# PCB.net
KiCad netlist of a schematic drawn in Altium Designer
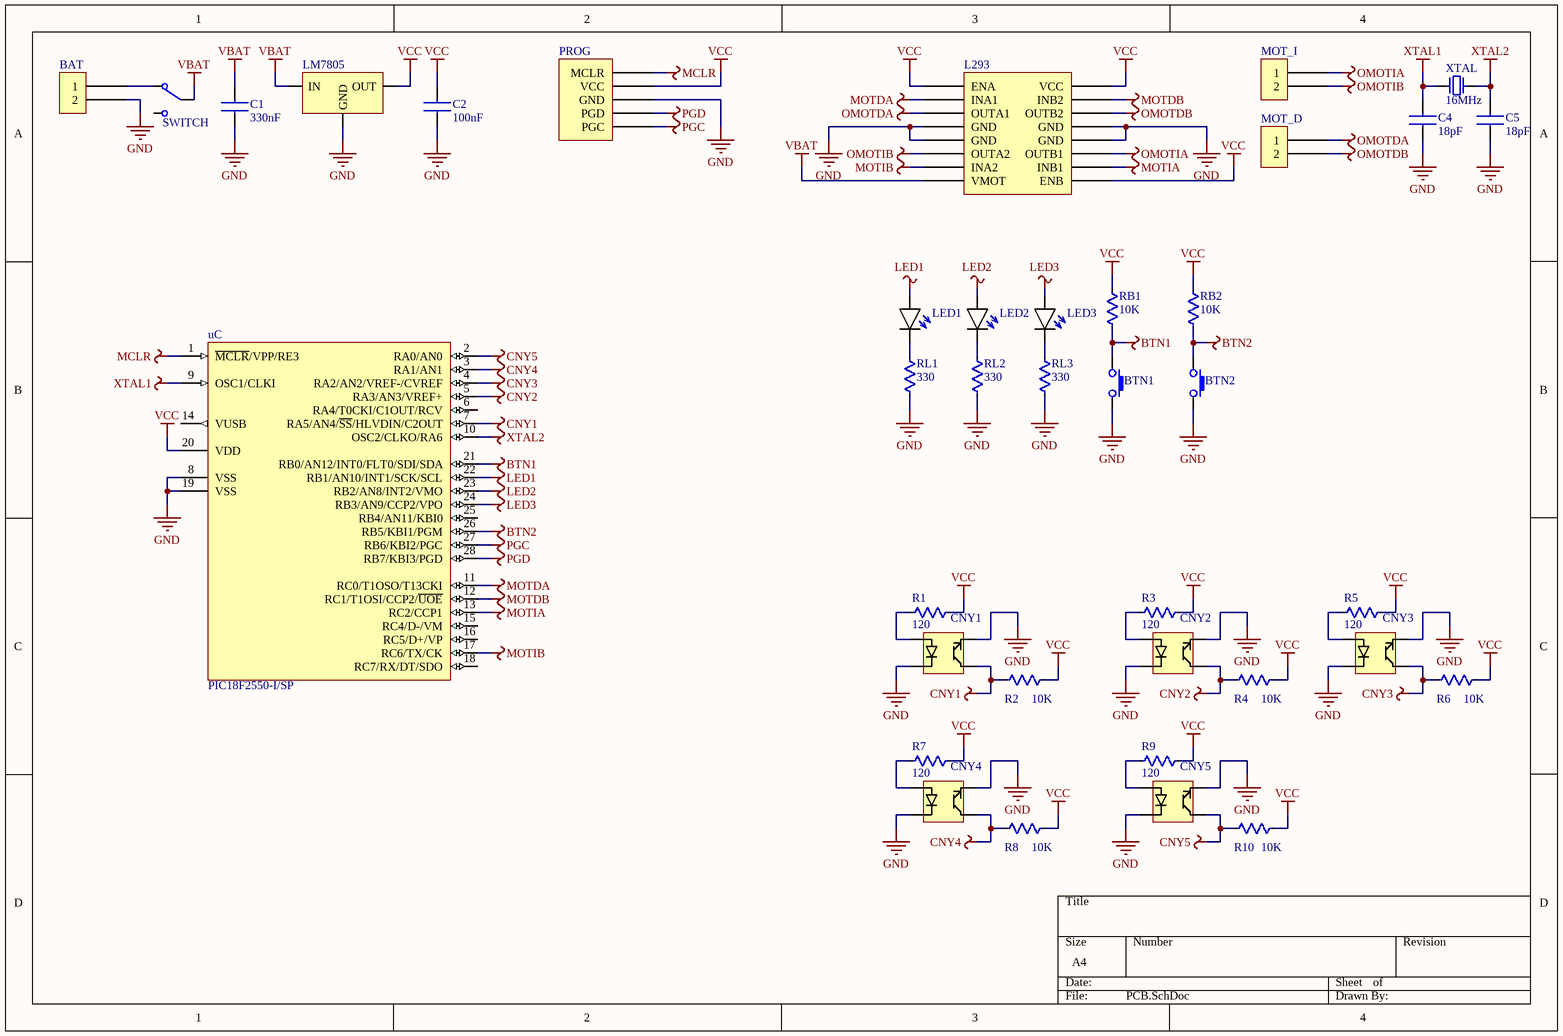
[diagram p0: PCB.SchDoc]

(export (version "E")
  (design (tool "Eeschema 10.0.6"))
  (components
    (comp (ref "BAT")
      (value "~")
      (footprint "HEADER 1x2")
      (libsource (lib "AltiumLibrary") (part "Header 1x2"))
    )
    (comp (ref "BTN1")
      (value "BUTTON_SMALL_4PIN")
      (footprint "TACT_SWITCH-SMALL-4PIN")
      (libsource (lib "AltiumLibrary") (part "BUTTON_SMALL_4PIN"))
    )
    (comp (ref "BTN2")
      (value "BUTTON_SMALL_4PIN")
      (footprint "TACT_SWITCH-SMALL-4PIN")
      (libsource (lib "AltiumLibrary") (part "BUTTON_SMALL_4PIN"))
    )
    (comp (ref "C1")
      (value "330nF")
      (footprint "CAP-CER")
      (fields (field (name "Comment") "CAP-CER"))
      (libsource (lib "AltiumLibrary") (part "CAP-CER"))
    )
    (comp (ref "C2")
      (value "100nF")
      (footprint "CAP-CER")
      (fields (field (name "Comment") "CAP-CER"))
      (libsource (lib "AltiumLibrary") (part "CAP-CER"))
    )
    (comp (ref "C4")
      (value "18pF")
      (footprint "CAP-CER")
      (fields (field (name "Comment") "CAP-CER"))
      (libsource (lib "AltiumLibrary") (part "CAP-CER"))
    )
    (comp (ref "C5")
      (value "18pF")
      (footprint "CAP-CER")
      (fields (field (name "Comment") "CAP-CER"))
      (libsource (lib "AltiumLibrary") (part "CAP-CER"))
    )
    (comp (ref "CNY1") (value "~") (footprint "CNY70") (libsource (lib "AltiumLibrary") (part "CNY70")))
    (comp (ref "CNY2") (value "~") (footprint "CNY70") (libsource (lib "AltiumLibrary") (part "CNY70")))
    (comp (ref "CNY3") (value "~") (footprint "CNY70") (libsource (lib "AltiumLibrary") (part "CNY70")))
    (comp (ref "CNY4") (value "~") (footprint "CNY70") (libsource (lib "AltiumLibrary") (part "CNY70")))
    (comp (ref "CNY5") (value "~") (footprint "CNY70") (libsource (lib "AltiumLibrary") (part "CNY70")))
    (comp (ref "L293") (value "L293") (footprint "DIP16") (libsource (lib "AltiumLibrary") (part "L293")))
    (comp (ref "LED1") (value "LED") (footprint "LED-3MM-RED") (libsource (lib "AltiumLibrary") (part "LED")))
    (comp (ref "LED2")
      (value "LED")
      (footprint "LED-3MM-YELLOW")
      (libsource (lib "AltiumLibrary") (part "LED"))
    )
    (comp (ref "LED3")
      (value "LED")
      (footprint "LED-3MM-GREEN")
      (libsource (lib "AltiumLibrary") (part "LED"))
    )
    (comp (ref "LM7805")
      (value "LM78XX")
      (footprint "TO-220-STRAIGHT")
      (libsource (lib "AltiumLibrary") (part "LM78XX"))
    )
    (comp (ref "MOT_D")
      (value "~")
      (footprint "HEADER 1x2")
      (libsource (lib "AltiumLibrary") (part "Header 1x2"))
    )
    (comp (ref "MOT_I")
      (value "~")
      (footprint "HEADER 1x2")
      (libsource (lib "AltiumLibrary") (part "Header 1x2"))
    )
    (comp (ref "PROG")
      (value "~")
      (footprint "Header 1x5")
      (libsource (lib "AltiumLibrary") (part "Header Programmer"))
    )
    (comp (ref "R1")
      (value "120")
      (footprint "RES-Axial-400mil")
      (fields (field (name "Comment") "RES"))
      (libsource (lib "AltiumLibrary") (part "RES"))
    )
    (comp (ref "R2")
      (value "10K")
      (footprint "RES-Axial-400mil")
      (fields (field (name "Comment") "RES"))
      (libsource (lib "AltiumLibrary") (part "RES"))
    )
    (comp (ref "R3")
      (value "120")
      (footprint "RES-Axial-400mil")
      (fields (field (name "Comment") "RES"))
      (libsource (lib "AltiumLibrary") (part "RES"))
    )
    (comp (ref "R4")
      (value "10K")
      (footprint "RES-Axial-400mil")
      (fields (field (name "Comment") "RES"))
      (libsource (lib "AltiumLibrary") (part "RES"))
    )
    (comp (ref "R5")
      (value "120")
      (footprint "RES-Axial-400mil")
      (fields (field (name "Comment") "RES"))
      (libsource (lib "AltiumLibrary") (part "RES"))
    )
    (comp (ref "R6")
      (value "10K")
      (footprint "RES-Axial-400mil")
      (fields (field (name "Comment") "RES"))
      (libsource (lib "AltiumLibrary") (part "RES"))
    )
    (comp (ref "R7")
      (value "120")
      (footprint "RES-Axial-400mil")
      (fields (field (name "Comment") "RES"))
      (libsource (lib "AltiumLibrary") (part "RES"))
    )
    (comp (ref "R8")
      (value "10K")
      (footprint "RES-Axial-400mil")
      (fields (field (name "Comment") "RES"))
      (libsource (lib "AltiumLibrary") (part "RES"))
    )
    (comp (ref "R9")
      (value "120")
      (footprint "RES-Axial-400mil")
      (fields (field (name "Comment") "RES"))
      (libsource (lib "AltiumLibrary") (part "RES"))
    )
    (comp (ref "R10")
      (value "10K")
      (footprint "RES-Axial-400mil")
      (fields (field (name "Comment") "RES"))
      (libsource (lib "AltiumLibrary") (part "RES"))
    )
    (comp (ref "RB1")
      (value "10K")
      (footprint "RES-Axial-400mil")
      (fields (field (name "Comment") "RES"))
      (libsource (lib "") (part "RES_1"))
    )
    (comp (ref "RB2")
      (value "10K")
      (footprint "RES-Axial-400mil")
      (fields (field (name "Comment") "RES"))
      (libsource (lib "") (part "RES_1"))
    )
    (comp (ref "RL1")
      (value "330")
      (footprint "RES-Axial-400mil")
      (fields (field (name "Comment") "RES"))
      (libsource (lib "") (part "RES_2"))
    )
    (comp (ref "RL2")
      (value "330")
      (footprint "RES-Axial-400mil")
      (fields (field (name "Comment") "RES"))
      (libsource (lib "") (part "RES_2"))
    )
    (comp (ref "RL3")
      (value "330")
      (footprint "RES-Axial-400mil")
      (fields (field (name "Comment") "RES"))
      (libsource (lib "") (part "RES_2"))
    )
    (comp (ref "SWITCH")
      (value "SLIDE-SWITCH")
      (footprint "SWITCH")
      (libsource (lib "AltiumLibrary") (part "SLIDE-SWITCH"))
    )
    (comp (ref "uC")
      (value "PIC18F2550-I/SP")
      (footprint "DIP28")
      (fields (field (name "PUBLISHER") "Altium Limited"))
      (libsource (lib "Microchip Microcontroller 8-Bit PIC18") (part "PIC18F2550-I/SP"))
    )
    (comp (ref "XTAL")
      (value "XTAL")
      (footprint "CRYSTAL-TH")
      (fields (field (name "FREQUENCY") "16MHz"))
      (libsource (lib "AltiumLibrary") (part "XTAL"))
    )
  )
  (nets
    (net (code "1") (name "BTN1") (class "Default")
      (node (ref "BTN1") (pin "1") (pintype "passive"))
      (node (ref "RB1") (pin "2") (pintype "passive"))
      (node (ref "uC") (pin "21") (pinfunction "RB0/AN12/INT0/FLT0/SDI/SDA_21") (pintype "bidirectional"))
    )
    (net (code "2") (name "BTN2") (class "Default")
      (node (ref "BTN2") (pin "1") (pintype "passive"))
      (node (ref "RB2") (pin "2") (pintype "passive"))
      (node (ref "uC") (pin "26") (pinfunction "RB5/KBI1/PGM_26") (pintype "bidirectional"))
    )
    (net (code "3") (name "CNY1") (class "Default")
      (node (ref "CNY1") (pin "C") (pinfunction "C_C") (pintype "passive"))
      (node (ref "R2") (pin "1") (pintype "passive"))
      (node (ref "uC") (pin "7") (pinfunction "RA5/AN4/~{SS}/HLVDIN/C2OUT_7") (pintype "bidirectional"))
    )
    (net (code "4") (name "CNY2") (class "Default")
      (node (ref "CNY2") (pin "C") (pinfunction "C_C") (pintype "passive"))
      (node (ref "R4") (pin "1") (pintype "passive"))
      (node (ref "uC") (pin "5") (pinfunction "RA3/AN3/VREF+_5") (pintype "bidirectional"))
    )
    (net (code "5") (name "CNY3") (class "Default")
      (node (ref "CNY3") (pin "C") (pinfunction "C_C") (pintype "passive"))
      (node (ref "R6") (pin "1") (pintype "passive"))
      (node (ref "uC") (pin "4") (pinfunction "RA2/AN2/VREF-/CVREF_4") (pintype "bidirectional"))
    )
    (net (code "6") (name "CNY4") (class "Default")
      (node (ref "CNY4") (pin "C") (pinfunction "C_C") (pintype "passive"))
      (node (ref "R8") (pin "1") (pintype "passive"))
      (node (ref "uC") (pin "3") (pinfunction "RA1/AN1_3") (pintype "bidirectional"))
    )
    (net (code "7") (name "CNY5") (class "Default")
      (node (ref "CNY5") (pin "C") (pinfunction "C_C") (pintype "passive"))
      (node (ref "R10") (pin "1") (pintype "passive"))
      (node (ref "uC") (pin "2") (pinfunction "RA0/AN0_2") (pintype "bidirectional"))
    )
    (net (code "8") (name "GND") (class "Default")
      (node (ref "BAT") (pin "2") (pinfunction "2_2") (pintype "passive"))
      (node (ref "BTN1") (pin "2") (pintype "passive"))
      (node (ref "BTN2") (pin "2") (pintype "passive"))
      (node (ref "C1") (pin "2") (pintype "passive"))
      (node (ref "C2") (pin "2") (pintype "passive"))
      (node (ref "C4") (pin "1") (pintype "passive"))
      (node (ref "C5") (pin "1") (pintype "passive"))
      (node (ref "CNY1") (pin "E") (pinfunction "7.5_E") (pintype "passive"))
      (node (ref "CNY1") (pin "K") (pinfunction "K_K") (pintype "passive"))
      (node (ref "CNY2") (pin "E") (pinfunction "7.5_E") (pintype "passive"))
      (node (ref "CNY2") (pin "K") (pinfunction "K_K") (pintype "passive"))
      (node (ref "CNY3") (pin "E") (pinfunction "7.5_E") (pintype "passive"))
      (node (ref "CNY3") (pin "K") (pinfunction "K_K") (pintype "passive"))
      (node (ref "CNY4") (pin "E") (pinfunction "7.5_E") (pintype "passive"))
      (node (ref "CNY4") (pin "K") (pinfunction "K_K") (pintype "passive"))
      (node (ref "CNY5") (pin "E") (pinfunction "7.5_E") (pintype "passive"))
      (node (ref "CNY5") (pin "K") (pinfunction "K_K") (pintype "passive"))
      (node (ref "L293") (pin "12") (pinfunction "GND_12") (pintype "passive"))
      (node (ref "L293") (pin "13") (pinfunction "GND_13") (pintype "passive"))
      (node (ref "L293") (pin "4") (pinfunction "GND_4") (pintype "passive"))
      (node (ref "L293") (pin "5") (pinfunction "GND_5") (pintype "passive"))
      (node (ref "LM7805") (pin "2") (pinfunction "GND_2") (pintype "power_in"))
      (node (ref "PROG") (pin "3") (pinfunction "GND_3") (pintype "power_in"))
      (node (ref "RL1") (pin "1") (pintype "passive"))
      (node (ref "RL2") (pin "1") (pintype "passive"))
      (node (ref "RL3") (pin "1") (pintype "passive"))
      (node (ref "uC") (pin "19") (pinfunction "VSS_19") (pintype "power_in"))
      (node (ref "uC") (pin "8") (pinfunction "VSS_8") (pintype "power_in"))
    )
    (net (code "9") (name "LED1") (class "Default")
      (node (ref "LED1") (pin "A") (pintype "passive"))
      (node (ref "uC") (pin "22") (pinfunction "RB1/AN10/INT1/SCK/SCL_22") (pintype "bidirectional"))
    )
    (net (code "10") (name "LED2") (class "Default")
      (node (ref "LED2") (pin "A") (pintype "passive"))
      (node (ref "uC") (pin "23") (pinfunction "RB2/AN8/INT2/VMO_23") (pintype "bidirectional"))
    )
    (net (code "11") (name "LED3") (class "Default")
      (node (ref "LED3") (pin "A") (pintype "passive"))
      (node (ref "uC") (pin "24") (pinfunction "RB3/AN9/CCP2/VPO_24") (pintype "bidirectional"))
    )
    (net (code "12") (name "MCLR") (class "Default")
      (node (ref "PROG") (pin "1") (pinfunction "MCLR_1") (pintype "passive"))
      (node (ref "uC") (pin "1") (pinfunction "~{MCLR}/VPP/RE3_1") (pintype "input"))
    )
    (net (code "13") (name "MOTDA") (class "Default")
      (node (ref "L293") (pin "2") (pinfunction "INA1_2") (pintype "passive"))
      (node (ref "uC") (pin "11") (pinfunction "RC0/T1OSO/T13CKI_11") (pintype "bidirectional"))
    )
    (net (code "14") (name "MOTDB") (class "Default")
      (node (ref "L293") (pin "15") (pinfunction "INB2_15") (pintype "passive"))
      (node (ref "uC") (pin "12") (pinfunction "RC1/T1OSI/CCP2/~{UOE}_12") (pintype "bidirectional"))
    )
    (net (code "15") (name "MOTIA") (class "Default")
      (node (ref "L293") (pin "10") (pinfunction "INB1_10") (pintype "passive"))
      (node (ref "uC") (pin "13") (pinfunction "RC2/CCP1_13") (pintype "bidirectional"))
    )
    (net (code "16") (name "MOTIB") (class "Default")
      (node (ref "L293") (pin "7") (pinfunction "INA2_7") (pintype "passive"))
      (node (ref "uC") (pin "17") (pinfunction "RC6/TX/CK_17") (pintype "bidirectional"))
    )
    (net (code "17") (name "Net-(BAT-Pad1)") (class "Default")
      (node (ref "BAT") (pin "1") (pinfunction "1_1") (pintype "passive"))
      (node (ref "SWITCH") (pin "1") (pintype "power_in"))
    )
    (net (code "18") (name "Net-(CNY1-PadA)") (class "Default")
      (node (ref "CNY1") (pin "A") (pinfunction "A_A") (pintype "passive"))
      (node (ref "R1") (pin "1") (pintype "passive"))
    )
    (net (code "19") (name "Net-(CNY2-PadA)") (class "Default")
      (node (ref "CNY2") (pin "A") (pinfunction "A_A") (pintype "passive"))
      (node (ref "R3") (pin "1") (pintype "passive"))
    )
    (net (code "20") (name "Net-(CNY3-PadA)") (class "Default")
      (node (ref "CNY3") (pin "A") (pinfunction "A_A") (pintype "passive"))
      (node (ref "R5") (pin "1") (pintype "passive"))
    )
    (net (code "21") (name "Net-(CNY4-PadA)") (class "Default")
      (node (ref "CNY4") (pin "A") (pinfunction "A_A") (pintype "passive"))
      (node (ref "R7") (pin "1") (pintype "passive"))
    )
    (net (code "22") (name "Net-(CNY5-PadA)") (class "Default")
      (node (ref "CNY5") (pin "A") (pinfunction "A_A") (pintype "passive"))
      (node (ref "R9") (pin "1") (pintype "passive"))
    )
    (net (code "23") (name "Net-(LED1-PadK)") (class "Default")
      (node (ref "LED1") (pin "K") (pintype "passive"))
      (node (ref "RL1") (pin "2") (pintype "passive"))
    )
    (net (code "24") (name "Net-(LED2-PadK)") (class "Default")
      (node (ref "LED2") (pin "K") (pintype "passive"))
      (node (ref "RL2") (pin "2") (pintype "passive"))
    )
    (net (code "25") (name "Net-(LED3-PadK)") (class "Default")
      (node (ref "LED3") (pin "K") (pintype "passive"))
      (node (ref "RL3") (pin "2") (pintype "passive"))
    )
    (net (code "26") (name "OMOTDA") (class "Default")
      (node (ref "L293") (pin "3") (pinfunction "OUTA1_3") (pintype "passive"))
      (node (ref "MOT_D") (pin "1") (pinfunction "1_1") (pintype "passive"))
    )
    (net (code "27") (name "OMOTDB") (class "Default")
      (node (ref "L293") (pin "14") (pinfunction "OUTB2_14") (pintype "passive"))
      (node (ref "MOT_D") (pin "2") (pinfunction "2_2") (pintype "passive"))
    )
    (net (code "28") (name "OMOTIA") (class "Default")
      (node (ref "L293") (pin "11") (pinfunction "OUTB1_11") (pintype "passive"))
      (node (ref "MOT_I") (pin "1") (pinfunction "1_1") (pintype "passive"))
    )
    (net (code "29") (name "OMOTIB") (class "Default")
      (node (ref "L293") (pin "6") (pinfunction "OUTA2_6") (pintype "passive"))
      (node (ref "MOT_I") (pin "2") (pinfunction "2_2") (pintype "passive"))
    )
    (net (code "30") (name "PGC") (class "Default")
      (node (ref "PROG") (pin "5") (pinfunction "PGC_5") (pintype "passive"))
      (node (ref "uC") (pin "27") (pinfunction "RB6/KBI2/PGC_27") (pintype "bidirectional"))
    )
    (net (code "31") (name "PGD") (class "Default")
      (node (ref "PROG") (pin "4") (pinfunction "PGD_4") (pintype "passive"))
      (node (ref "uC") (pin "28") (pinfunction "RB7/KBI3/PGD_28") (pintype "bidirectional"))
    )
    (net (code "32") (name "VBAT") (class "Default")
      (node (ref "C1") (pin "1") (pintype "passive"))
      (node (ref "L293") (pin "8") (pinfunction "VMOT_8") (pintype "passive"))
      (node (ref "LM7805") (pin "1") (pinfunction "IN_1") (pintype "power_in"))
      (node (ref "SWITCH") (pin "2") (pintype "power_in"))
    )
    (net (code "33") (name "VCC") (class "Default")
      (node (ref "C2") (pin "1") (pintype "passive"))
      (node (ref "L293") (pin "1") (pinfunction "ENA_1") (pintype "passive"))
      (node (ref "L293") (pin "16") (pinfunction "VCC_16") (pintype "passive"))
      (node (ref "L293") (pin "9") (pinfunction "ENB_9") (pintype "passive"))
      (node (ref "LM7805") (pin "3") (pinfunction "OUT_3") (pintype "power_in"))
      (node (ref "PROG") (pin "2") (pinfunction "VCC_2") (pintype "power_in"))
      (node (ref "R1") (pin "2") (pintype "passive"))
      (node (ref "R10") (pin "2") (pintype "passive"))
      (node (ref "R2") (pin "2") (pintype "passive"))
      (node (ref "R3") (pin "2") (pintype "passive"))
      (node (ref "R4") (pin "2") (pintype "passive"))
      (node (ref "R5") (pin "2") (pintype "passive"))
      (node (ref "R6") (pin "2") (pintype "passive"))
      (node (ref "R7") (pin "2") (pintype "passive"))
      (node (ref "R8") (pin "2") (pintype "passive"))
      (node (ref "R9") (pin "2") (pintype "passive"))
      (node (ref "RB1") (pin "1") (pintype "passive"))
      (node (ref "RB2") (pin "1") (pintype "passive"))
      (node (ref "uC") (pin "20") (pinfunction "VDD_20") (pintype "power_in"))
    )
    (net (code "34") (name "XTAL1") (class "Default")
      (node (ref "C4") (pin "2") (pintype "passive"))
      (node (ref "XTAL") (pin "1") (pintype "passive"))
      (node (ref "uC") (pin "9") (pinfunction "OSC1/CLKI_9") (pintype "input"))
    )
    (net (code "35") (name "XTAL2") (class "Default")
      (node (ref "C5") (pin "2") (pintype "passive"))
      (node (ref "XTAL") (pin "2") (pintype "passive"))
      (node (ref "uC") (pin "10") (pinfunction "OSC2/CLKO/RA6_10") (pintype "bidirectional"))
    )
    (net (code "36") (name "unconnected-(SWITCH-Pad3)") (class "Default")
      (node (ref "SWITCH") (pin "3") (pintype "power_in"))
    )
    (net (code "37") (name "unconnected-(uC-RA4{slash}T0CKI{slash}C1OUT{slash}RCV-Pad6)") (class "Default")
      (node (ref "uC") (pin "6") (pinfunction "RA4/T0CKI/C1OUT/RCV_6") (pintype "bidirectional"))
    )
    (net (code "38") (name "unconnected-(uC-RB4{slash}AN11{slash}KBI0-Pad25)") (class "Default")
      (node (ref "uC") (pin "25") (pinfunction "RB4/AN11/KBI0_25") (pintype "bidirectional"))
    )
    (net (code "39") (name "unconnected-(uC-RC4{slash}D-{slash}VM-Pad15)") (class "Default")
      (node (ref "uC") (pin "15") (pinfunction "RC4/D-/VM_15") (pintype "bidirectional"))
    )
    (net (code "40") (name "unconnected-(uC-RC5{slash}D+{slash}VP-Pad16)") (class "Default")
      (node (ref "uC") (pin "16") (pinfunction "RC5/D+/VP_16") (pintype "bidirectional"))
    )
    (net (code "41") (name "unconnected-(uC-RC7{slash}RX{slash}DT{slash}SDO-Pad18)") (class "Default")
      (node (ref "uC") (pin "18") (pinfunction "RC7/RX/DT/SDO_18") (pintype "bidirectional"))
    )
    (net (code "42") (name "unconnected-(uC-VUSB-Pad14)") (class "Default")
      (node (ref "uC") (pin "14") (pinfunction "VUSB_14") (pintype "output"))
    )
  )
)
